# motorplank.net
KiCad netlist of a schematic drawn in EAGLE
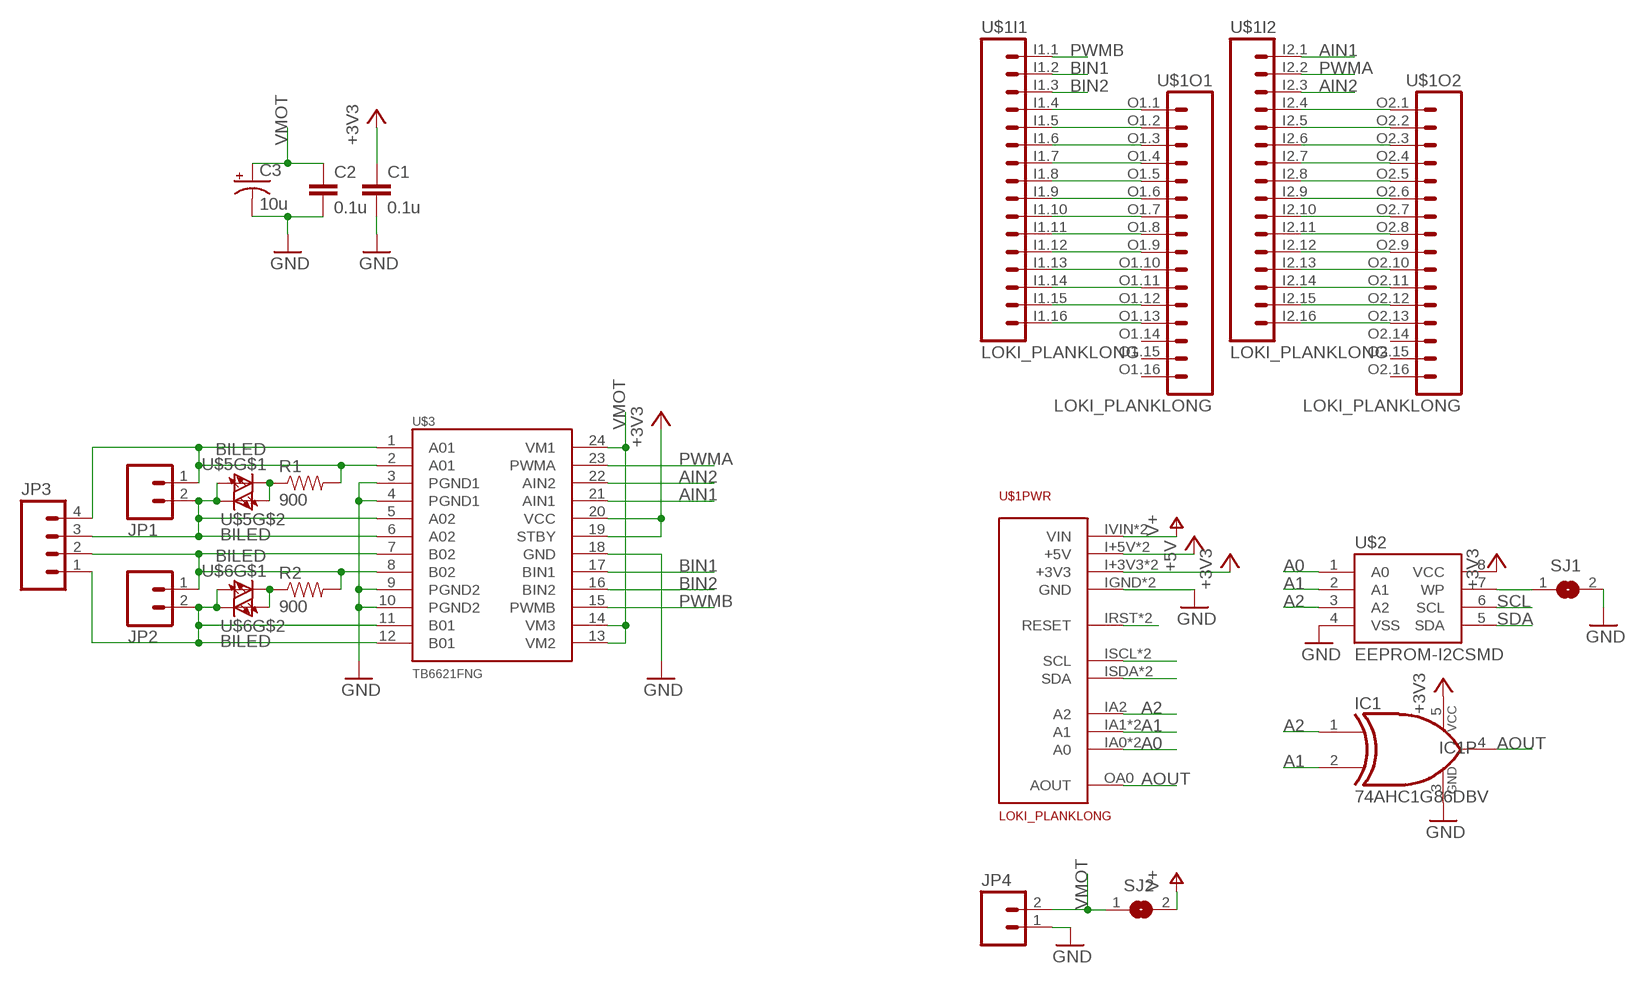
[diagram p0: schematic, sheet 1]

(export (version "E")
  (design (tool "Eeschema 10.0.6"))
  (components
    (comp (ref "C1")
      (value "0.1u")
      (footprint "eagle-import:0805")
      (libsource (lib "eagle-import") (part "CAP0805"))
    )
    (comp (ref "C2")
      (value "0.1u")
      (footprint "eagle-import:0805")
      (libsource (lib "eagle-import") (part "CAP0805"))
    )
    (comp (ref "C3")
      (value "10u")
      (footprint "eagle-import:PANASONIC_C")
      (libsource (lib "eagle-import") (part "CAP_POLC"))
    )
    (comp (ref "IC1")
      (value "74AHC1G86DBV")
      (footprint "eagle-import:SOT23-5")
      (libsource (lib "eagle-import") (part "741G86DBVAHC"))
    )
    (comp (ref "JP1")
      (value "M023.5MM")
      (footprint "eagle-import:SCREWTERMINAL-3.5MM-2")
      (libsource (lib "eagle-import") (part "M023.5MM"))
    )
    (comp (ref "JP2")
      (value "M023.5MM")
      (footprint "eagle-import:SCREWTERMINAL-3.5MM-2")
      (libsource (lib "eagle-import") (part "M023.5MM"))
    )
    (comp (ref "JP3")
      (value "M04PTH")
      (footprint "eagle-import:1X04")
      (libsource (lib "eagle-import") (part "M04PTH"))
    )
    (comp (ref "JP4")
      (value "M023.5MM")
      (footprint "eagle-import:SCREWTERMINAL-3.5MM-2")
      (libsource (lib "eagle-import") (part "M023.5MM"))
    )
    (comp (ref "R1")
      (value "900")
      (footprint "eagle-import:0805")
      (libsource (lib "eagle-import") (part "RESISTOR0805-RES"))
    )
    (comp (ref "R2")
      (value "900")
      (footprint "eagle-import:0805")
      (libsource (lib "eagle-import") (part "RESISTOR0805-RES"))
    )
    (comp (ref "SJ1") (value "SJ") (footprint "eagle-import:SJ") (libsource (lib "eagle-import") (part "SJ")))
    (comp (ref "SJ2") (value "SJ") (footprint "eagle-import:SJ") (libsource (lib "eagle-import") (part "SJ")))
    (comp (ref "U$1")
      (value "LOKI_PLANKLONG")
      (footprint "eagle-import:PLANK_LONG")
      (libsource (lib "eagle-import") (part "LOKI_PLANKLONG"))
    )
    (comp (ref "U$2")
      (value "EEPROM-I2CSMD")
      (footprint "eagle-import:SO08")
      (libsource (lib "eagle-import") (part "EEPROM-I2CSMD"))
    )
    (comp (ref "U$3")
      (value "TB6621FNG")
      (footprint "eagle-import:SSOP24")
      (libsource (lib "eagle-import") (part "TB6621FNG"))
    )
    (comp (ref "U$5")
      (value "BILED")
      (footprint "eagle-import:BILED")
      (libsource (lib "eagle-import") (part "BILED"))
    )
    (comp (ref "U$6")
      (value "BILED")
      (footprint "eagle-import:BILED")
      (libsource (lib "eagle-import") (part "BILED"))
    )
  )
  (nets
    (net (code "1") (name "+3V3") (class "Default")
      (node (ref "C1") (pin "1") (pinfunction "1_1") (pintype "passive"))
      (node (ref "IC1") (pin "5") (pinfunction "VCC_5") (pintype "power_in"))
      (node (ref "U$1") (pin "I+3V3") (pinfunction "+3V3_I+3V3") (pintype "power_in"))
      (node (ref "U$1") (pin "O+3V3") (pinfunction "+3V3_O+3V3") (pintype "power_in"))
      (node (ref "U$2") (pin "8") (pinfunction "VCC_8") (pintype "power_in"))
      (node (ref "U$3") (pin "19") (pinfunction "STBY_19") (pintype "bidirectional"))
      (node (ref "U$3") (pin "20") (pinfunction "VCC_20") (pintype "bidirectional"))
    )
    (net (code "2") (name "+5V") (class "Default")
      (node (ref "U$1") (pin "I+5V") (pinfunction "+5V_I+5V") (pintype "power_in"))
      (node (ref "U$1") (pin "O+5V") (pinfunction "+5V_O+5V") (pintype "power_in"))
    )
    (net (code "3") (name "/A0") (class "Default")
      (node (ref "U$1") (pin "IA0") (pinfunction "A0_IA0") (pintype "output"))
      (node (ref "U$1") (pin "OA1") (pinfunction "A0_OA1") (pintype "output"))
      (node (ref "U$2") (pin "1") (pinfunction "A0_1") (pintype "bidirectional"))
    )
    (net (code "4") (name "/A1") (class "Default")
      (node (ref "IC1") (pin "2") (pinfunction "I1_2") (pintype "input"))
      (node (ref "U$1") (pin "IA1") (pinfunction "A1_IA1") (pintype "output"))
      (node (ref "U$1") (pin "OA2") (pinfunction "A1_OA2") (pintype "output"))
      (node (ref "U$2") (pin "2") (pinfunction "A1_2") (pintype "bidirectional"))
    )
    (net (code "5") (name "/A2") (class "Default")
      (node (ref "IC1") (pin "1") (pinfunction "I0_1") (pintype "input"))
      (node (ref "U$1") (pin "IA2") (pinfunction "A2_IA2") (pintype "output"))
      (node (ref "U$2") (pin "3") (pinfunction "A2_3") (pintype "bidirectional"))
    )
    (net (code "6") (name "/AIN1") (class "Default")
      (node (ref "U$1") (pin "I2.1") (pinfunction "1_I2.1") (pintype "passive"))
      (node (ref "U$3") (pin "21") (pinfunction "AIN1_21") (pintype "bidirectional"))
    )
    (net (code "7") (name "/AIN2") (class "Default")
      (node (ref "U$1") (pin "I2.3") (pinfunction "3_I2.3") (pintype "passive"))
      (node (ref "U$3") (pin "22") (pinfunction "AIN2_22") (pintype "bidirectional"))
    )
    (net (code "8") (name "/AOUT") (class "Default")
      (node (ref "IC1") (pin "4") (pinfunction "O_4") (pintype "output"))
      (node (ref "U$1") (pin "OA0") (pinfunction "AOUT_OA0") (pintype "input"))
    )
    (net (code "9") (name "/BIN1") (class "Default")
      (node (ref "U$1") (pin "I1.2") (pinfunction "2_I1.2") (pintype "passive"))
      (node (ref "U$3") (pin "17") (pinfunction "BIN1_17") (pintype "bidirectional"))
    )
    (net (code "10") (name "/BIN2") (class "Default")
      (node (ref "U$1") (pin "I1.3") (pinfunction "3_I1.3") (pintype "passive"))
      (node (ref "U$3") (pin "16") (pinfunction "BIN2_16") (pintype "bidirectional"))
    )
    (net (code "11") (name "/PWMA") (class "Default")
      (node (ref "U$1") (pin "I2.2") (pinfunction "2_I2.2") (pintype "passive"))
      (node (ref "U$3") (pin "23") (pinfunction "PWMA_23") (pintype "bidirectional"))
    )
    (net (code "12") (name "/PWMB") (class "Default")
      (node (ref "U$1") (pin "I1.1") (pinfunction "1_I1.1") (pintype "passive"))
      (node (ref "U$3") (pin "15") (pinfunction "PWMB_15") (pintype "bidirectional"))
    )
    (net (code "13") (name "/SCL") (class "Default")
      (node (ref "U$1") (pin "ISCL") (pinfunction "SCL_ISCL") (pintype "bidirectional"))
      (node (ref "U$1") (pin "OSCL") (pinfunction "SCL_OSCL") (pintype "bidirectional"))
      (node (ref "U$2") (pin "6") (pinfunction "SCL_6") (pintype "bidirectional"))
    )
    (net (code "14") (name "/SDA") (class "Default")
      (node (ref "U$1") (pin "ISDA") (pinfunction "SDA_ISDA") (pintype "bidirectional"))
      (node (ref "U$1") (pin "OSDA") (pinfunction "SDA_OSDA") (pintype "bidirectional"))
      (node (ref "U$2") (pin "5") (pinfunction "SDA_5") (pintype "bidirectional"))
    )
    (net (code "15") (name "/VMOT") (class "Default")
      (node (ref "C2") (pin "1") (pinfunction "1_1") (pintype "passive"))
      (node (ref "C3") (pin "+") (pinfunction "+_+") (pintype "passive"))
      (node (ref "JP4") (pin "2") (pinfunction "2_2") (pintype "passive"))
      (node (ref "SJ2") (pin "1") (pinfunction "1_1") (pintype "passive"))
      (node (ref "U$3") (pin "13") (pinfunction "VM2_13") (pintype "bidirectional"))
      (node (ref "U$3") (pin "14") (pinfunction "VM3_14") (pintype "bidirectional"))
      (node (ref "U$3") (pin "24") (pinfunction "VM1_24") (pintype "bidirectional"))
    )
    (net (code "16") (name "GND") (class "Default")
      (node (ref "C1") (pin "2") (pinfunction "2_2") (pintype "passive"))
      (node (ref "C2") (pin "2") (pinfunction "2_2") (pintype "passive"))
      (node (ref "C3") (pin "-") (pinfunction "-_-") (pintype "passive"))
      (node (ref "IC1") (pin "3") (pinfunction "GND_3") (pintype "power_in"))
      (node (ref "JP4") (pin "1") (pinfunction "1_1") (pintype "passive"))
      (node (ref "SJ1") (pin "2") (pinfunction "2_2") (pintype "passive"))
      (node (ref "U$1") (pin "IGND") (pinfunction "GND_IGND") (pintype "power_in"))
      (node (ref "U$1") (pin "OGND") (pinfunction "GND_OGND") (pintype "power_in"))
      (node (ref "U$2") (pin "4") (pinfunction "VSS_4") (pintype "power_in"))
      (node (ref "U$3") (pin "10") (pinfunction "PGND2_10") (pintype "bidirectional"))
      (node (ref "U$3") (pin "18") (pinfunction "GND_18") (pintype "bidirectional"))
      (node (ref "U$3") (pin "3") (pinfunction "PGND1_3") (pintype "bidirectional"))
      (node (ref "U$3") (pin "4") (pinfunction "PGND1_4") (pintype "bidirectional"))
      (node (ref "U$3") (pin "9") (pinfunction "PGND2_9") (pintype "bidirectional"))
    )
    (net (code "17") (name "Net-(JP1-Pad1)") (class "Default")
      (node (ref "JP1") (pin "1") (pinfunction "1_1") (pintype "passive"))
      (node (ref "JP3") (pin "4") (pinfunction "4_4") (pintype "passive"))
      (node (ref "R1") (pin "2") (pinfunction "2_2") (pintype "passive"))
      (node (ref "U$3") (pin "1") (pinfunction "A01_1") (pintype "bidirectional"))
      (node (ref "U$3") (pin "2") (pinfunction "A01_2") (pintype "bidirectional"))
    )
    (net (code "18") (name "Net-(JP2-Pad1)") (class "Default")
      (node (ref "JP2") (pin "1") (pinfunction "1_1") (pintype "passive"))
      (node (ref "JP3") (pin "2") (pinfunction "2_2") (pintype "passive"))
      (node (ref "R2") (pin "2") (pinfunction "2_2") (pintype "passive"))
      (node (ref "U$3") (pin "7") (pinfunction "B02_7") (pintype "bidirectional"))
      (node (ref "U$3") (pin "8") (pinfunction "B02_8") (pintype "bidirectional"))
    )
    (net (code "19") (name "Net-(U$1A-4)") (class "Default")
      (node (ref "U$1") (pin "I1.4") (pinfunction "4_I1.4") (pintype "passive"))
      (node (ref "U$1") (pin "O1.1") (pinfunction "1_O1.1") (pintype "passive"))
    )
    (net (code "20") (name "Net-(U$1A-5)") (class "Default")
      (node (ref "U$1") (pin "I1.5") (pinfunction "5_I1.5") (pintype "passive"))
      (node (ref "U$1") (pin "O1.2") (pinfunction "2_O1.2") (pintype "passive"))
    )
    (net (code "21") (name "Net-(U$1A-6)") (class "Default")
      (node (ref "U$1") (pin "I1.6") (pinfunction "6_I1.6") (pintype "passive"))
      (node (ref "U$1") (pin "O1.3") (pinfunction "3_O1.3") (pintype "passive"))
    )
    (net (code "22") (name "Net-(U$1A-7)") (class "Default")
      (node (ref "U$1") (pin "I1.7") (pinfunction "7_I1.7") (pintype "passive"))
      (node (ref "U$1") (pin "O1.4") (pinfunction "4_O1.4") (pintype "passive"))
    )
    (net (code "23") (name "Net-(U$1A-8)") (class "Default")
      (node (ref "U$1") (pin "I1.8") (pinfunction "8_I1.8") (pintype "passive"))
      (node (ref "U$1") (pin "O1.5") (pinfunction "5_O1.5") (pintype "passive"))
    )
    (net (code "24") (name "Net-(U$1A-9)") (class "Default")
      (node (ref "U$1") (pin "I1.9") (pinfunction "9_I1.9") (pintype "passive"))
      (node (ref "U$1") (pin "O1.6") (pinfunction "6_O1.6") (pintype "passive"))
    )
    (net (code "25") (name "Net-(U$1A-10)") (class "Default")
      (node (ref "U$1") (pin "I1.10") (pinfunction "10_I1.10") (pintype "passive"))
      (node (ref "U$1") (pin "O1.7") (pinfunction "7_O1.7") (pintype "passive"))
    )
    (net (code "26") (name "Net-(U$1A-11)") (class "Default")
      (node (ref "U$1") (pin "I1.11") (pinfunction "11_I1.11") (pintype "passive"))
      (node (ref "U$1") (pin "O1.8") (pinfunction "8_O1.8") (pintype "passive"))
    )
    (net (code "27") (name "Net-(U$1A-12)") (class "Default")
      (node (ref "U$1") (pin "I1.12") (pinfunction "12_I1.12") (pintype "passive"))
      (node (ref "U$1") (pin "O1.9") (pinfunction "9_O1.9") (pintype "passive"))
    )
    (net (code "28") (name "Net-(U$1A-13)") (class "Default")
      (node (ref "U$1") (pin "I1.13") (pinfunction "13_I1.13") (pintype "passive"))
      (node (ref "U$1") (pin "O1.10") (pinfunction "10_O1.10") (pintype "passive"))
    )
    (net (code "29") (name "Net-(U$1A-14)") (class "Default")
      (node (ref "U$1") (pin "I1.14") (pinfunction "14_I1.14") (pintype "passive"))
      (node (ref "U$1") (pin "O1.11") (pinfunction "11_O1.11") (pintype "passive"))
    )
    (net (code "30") (name "Net-(U$1A-15)") (class "Default")
      (node (ref "U$1") (pin "I1.15") (pinfunction "15_I1.15") (pintype "passive"))
      (node (ref "U$1") (pin "O1.12") (pinfunction "12_O1.12") (pintype "passive"))
    )
    (net (code "31") (name "Net-(U$1A-16)") (class "Default")
      (node (ref "U$1") (pin "I1.16") (pinfunction "16_I1.16") (pintype "passive"))
      (node (ref "U$1") (pin "O1.13") (pinfunction "13_O1.13") (pintype "passive"))
    )
    (net (code "32") (name "Net-(U$1B-4)") (class "Default")
      (node (ref "U$1") (pin "I2.4") (pinfunction "4_I2.4") (pintype "passive"))
      (node (ref "U$1") (pin "O2.1") (pinfunction "1_O2.1") (pintype "passive"))
    )
    (net (code "33") (name "Net-(U$1B-5)") (class "Default")
      (node (ref "U$1") (pin "I2.5") (pinfunction "5_I2.5") (pintype "passive"))
      (node (ref "U$1") (pin "O2.2") (pinfunction "2_O2.2") (pintype "passive"))
    )
    (net (code "34") (name "Net-(U$1B-6)") (class "Default")
      (node (ref "U$1") (pin "I2.6") (pinfunction "6_I2.6") (pintype "passive"))
      (node (ref "U$1") (pin "O2.3") (pinfunction "3_O2.3") (pintype "passive"))
    )
    (net (code "35") (name "Net-(U$1B-7)") (class "Default")
      (node (ref "U$1") (pin "I2.7") (pinfunction "7_I2.7") (pintype "passive"))
      (node (ref "U$1") (pin "O2.4") (pinfunction "4_O2.4") (pintype "passive"))
    )
    (net (code "36") (name "Net-(U$1B-8)") (class "Default")
      (node (ref "U$1") (pin "I2.8") (pinfunction "8_I2.8") (pintype "passive"))
      (node (ref "U$1") (pin "O2.5") (pinfunction "5_O2.5") (pintype "passive"))
    )
    (net (code "37") (name "Net-(U$1B-9)") (class "Default")
      (node (ref "U$1") (pin "I2.9") (pinfunction "9_I2.9") (pintype "passive"))
      (node (ref "U$1") (pin "O2.6") (pinfunction "6_O2.6") (pintype "passive"))
    )
    (net (code "38") (name "Net-(U$1B-10)") (class "Default")
      (node (ref "U$1") (pin "I2.10") (pinfunction "10_I2.10") (pintype "passive"))
      (node (ref "U$1") (pin "O2.7") (pinfunction "7_O2.7") (pintype "passive"))
    )
    (net (code "39") (name "Net-(U$1B-11)") (class "Default")
      (node (ref "U$1") (pin "I2.11") (pinfunction "11_I2.11") (pintype "passive"))
      (node (ref "U$1") (pin "O2.8") (pinfunction "8_O2.8") (pintype "passive"))
    )
    (net (code "40") (name "Net-(U$1B-12)") (class "Default")
      (node (ref "U$1") (pin "I2.12") (pinfunction "12_I2.12") (pintype "passive"))
      (node (ref "U$1") (pin "O2.9") (pinfunction "9_O2.9") (pintype "passive"))
    )
    (net (code "41") (name "Net-(U$1B-13)") (class "Default")
      (node (ref "U$1") (pin "I2.13") (pinfunction "13_I2.13") (pintype "passive"))
      (node (ref "U$1") (pin "O2.10") (pinfunction "10_O2.10") (pintype "passive"))
    )
    (net (code "42") (name "Net-(U$1B-14)") (class "Default")
      (node (ref "U$1") (pin "I2.14") (pinfunction "14_I2.14") (pintype "passive"))
      (node (ref "U$1") (pin "O2.11") (pinfunction "11_O2.11") (pintype "passive"))
    )
    (net (code "43") (name "Net-(U$1B-15)") (class "Default")
      (node (ref "U$1") (pin "I2.15") (pinfunction "15_I2.15") (pintype "passive"))
      (node (ref "U$1") (pin "O2.12") (pinfunction "12_O2.12") (pintype "passive"))
    )
    (net (code "44") (name "Net-(U$1B-16)") (class "Default")
      (node (ref "U$1") (pin "I2.16") (pinfunction "16_I2.16") (pintype "passive"))
      (node (ref "U$1") (pin "O2.13") (pinfunction "13_O2.13") (pintype "passive"))
    )
    (net (code "45") (name "Net-(U$1E-RESET-PadIRST)") (class "Default")
      (node (ref "U$1") (pin "IRST") (pinfunction "RESET_IRST") (pintype "input"))
      (node (ref "U$1") (pin "ORST") (pinfunction "RESET_ORST") (pintype "input"))
    )
    (net (code "46") (name "Net-(U$2-WP)") (class "Default")
      (node (ref "SJ1") (pin "1") (pinfunction "1_1") (pintype "passive"))
      (node (ref "U$2") (pin "7") (pinfunction "WP_7") (pintype "bidirectional"))
    )
    (net (code "47") (name "Net-(U$5A-A)") (class "Default")
      (node (ref "JP1") (pin "2") (pinfunction "2_2") (pintype "passive"))
      (node (ref "JP3") (pin "3") (pinfunction "3_3") (pintype "passive"))
      (node (ref "U$3") (pin "5") (pinfunction "A02_5") (pintype "bidirectional"))
      (node (ref "U$3") (pin "6") (pinfunction "A02_6") (pintype "bidirectional"))
      (node (ref "U$5") (pin "A1") (pinfunction "A_A1") (pintype "passive"))
      (node (ref "U$5") (pin "C2") (pinfunction "C_C2") (pintype "passive"))
    )
    (net (code "48") (name "Net-(U$5A-C)") (class "Default")
      (node (ref "R1") (pin "1") (pinfunction "1_1") (pintype "passive"))
      (node (ref "U$5") (pin "A2") (pinfunction "A_A2") (pintype "passive"))
      (node (ref "U$5") (pin "C1") (pinfunction "C_C1") (pintype "passive"))
    )
    (net (code "49") (name "Net-(U$6A-A)") (class "Default")
      (node (ref "JP2") (pin "2") (pinfunction "2_2") (pintype "passive"))
      (node (ref "JP3") (pin "1") (pinfunction "1_1") (pintype "passive"))
      (node (ref "U$3") (pin "11") (pinfunction "B01_11") (pintype "bidirectional"))
      (node (ref "U$3") (pin "12") (pinfunction "B01_12") (pintype "bidirectional"))
      (node (ref "U$6") (pin "A1") (pinfunction "A_A1") (pintype "passive"))
      (node (ref "U$6") (pin "C2") (pinfunction "C_C2") (pintype "passive"))
    )
    (net (code "50") (name "Net-(U$6A-C)") (class "Default")
      (node (ref "R2") (pin "1") (pinfunction "1_1") (pintype "passive"))
      (node (ref "U$6") (pin "A2") (pinfunction "A_A2") (pintype "passive"))
      (node (ref "U$6") (pin "C1") (pinfunction "C_C1") (pintype "passive"))
    )
    (net (code "51") (name "V+") (class "Default")
      (node (ref "SJ2") (pin "2") (pinfunction "2_2") (pintype "passive"))
      (node (ref "U$1") (pin "IVIN") (pinfunction "VIN_IVIN") (pintype "power_in"))
      (node (ref "U$1") (pin "OVIN") (pinfunction "VIN_OVIN") (pintype "power_in"))
    )
    (net (code "52") (name "unconnected-(U$1C-14-PadO1.14)") (class "Default")
      (node (ref "U$1") (pin "O1.14") (pinfunction "14_O1.14") (pintype "passive"))
    )
    (net (code "53") (name "unconnected-(U$1C-15-PadO1.15)") (class "Default")
      (node (ref "U$1") (pin "O1.15") (pinfunction "15_O1.15") (pintype "passive"))
    )
    (net (code "54") (name "unconnected-(U$1C-16-PadO1.16)") (class "Default")
      (node (ref "U$1") (pin "O1.16") (pinfunction "16_O1.16") (pintype "passive"))
    )
    (net (code "55") (name "unconnected-(U$1D-14-PadO2.14)") (class "Default")
      (node (ref "U$1") (pin "O2.14") (pinfunction "14_O2.14") (pintype "passive"))
    )
    (net (code "56") (name "unconnected-(U$1D-15-PadO2.15)") (class "Default")
      (node (ref "U$1") (pin "O2.15") (pinfunction "15_O2.15") (pintype "passive"))
    )
    (net (code "57") (name "unconnected-(U$1D-16-PadO2.16)") (class "Default")
      (node (ref "U$1") (pin "O2.16") (pinfunction "16_O2.16") (pintype "passive"))
    )
  )
)
